# main.net
KiCad netlist of a schematic drawn in Altium Designer
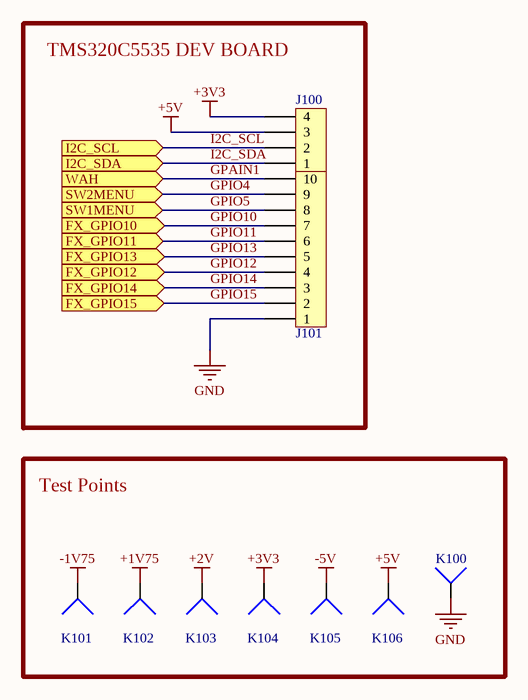
[diagram p0: main.SchDoc]

(export (version "E")
  (design (tool "Eeschema 10.0.6"))
  (components
    (comp (ref "J100")
      (value "Header 1x4")
      (footprint "Header 1x4")
      (libsource (lib "AAURacing") (part "Header 1x4"))
    )
    (comp (ref "J101")
      (value "Header 1x10")
      (footprint "Header 1x10")
      (libsource (lib "AAURacing") (part "Header 1x10"))
    )
    (comp (ref "K100") (value "Wire") (footprint "Wire 1.5mm") (libsource (lib "AAURacing") (part "Wire")))
    (comp (ref "K101") (value "Wire") (footprint "Wire 1.5mm") (libsource (lib "AAURacing") (part "Wire")))
    (comp (ref "K102") (value "Wire") (footprint "Wire 1.5mm") (libsource (lib "AAURacing") (part "Wire")))
    (comp (ref "K103") (value "Wire") (footprint "Wire 1.5mm") (libsource (lib "AAURacing") (part "Wire")))
    (comp (ref "K104") (value "Wire") (footprint "Wire 1.5mm") (libsource (lib "AAURacing") (part "Wire")))
    (comp (ref "K105") (value "Wire") (footprint "Wire 1.5mm") (libsource (lib "AAURacing") (part "Wire")))
    (comp (ref "K106") (value "Wire") (footprint "Wire 1.5mm") (libsource (lib "AAURacing") (part "Wire")))
  )
  (nets
    (net (code "1") (name "+1V75") (class "Default")
      (node (ref "K102") (pin "1") (pinfunction "1_1") (pintype "passive"))
    )
    (net (code "2") (name "+2V") (class "Default")
      (node (ref "K103") (pin "1") (pinfunction "1_1") (pintype "passive"))
    )
    (net (code "3") (name "+3V3") (class "Default")
      (node (ref "J100") (pin "4") (pinfunction "4_4") (pintype "passive"))
      (node (ref "K104") (pin "1") (pinfunction "1_1") (pintype "passive"))
    )
    (net (code "4") (name "+5V") (class "Default")
      (node (ref "J100") (pin "3") (pinfunction "3_3") (pintype "passive"))
      (node (ref "K106") (pin "1") (pinfunction "1_1") (pintype "passive"))
    )
    (net (code "5") (name "-1V75") (class "Default")
      (node (ref "K101") (pin "1") (pinfunction "1_1") (pintype "passive"))
    )
    (net (code "6") (name "-5V") (class "Default")
      (node (ref "K105") (pin "1") (pinfunction "1_1") (pintype "passive"))
    )
    (net (code "7") (name "/GPAIN1") (class "Default")
      (node (ref "J101") (pin "10") (pinfunction "10_10") (pintype "passive"))
    )
    (net (code "8") (name "/GPIO4") (class "Default")
      (node (ref "J101") (pin "9") (pinfunction "9_9") (pintype "passive"))
    )
    (net (code "9") (name "/GPIO5") (class "Default")
      (node (ref "J101") (pin "8") (pinfunction "8_8") (pintype "passive"))
    )
    (net (code "10") (name "/GPIO10") (class "Default")
      (node (ref "J101") (pin "7") (pinfunction "7_7") (pintype "passive"))
    )
    (net (code "11") (name "/GPIO11") (class "Default")
      (node (ref "J101") (pin "6") (pinfunction "6_6") (pintype "passive"))
    )
    (net (code "12") (name "/GPIO12") (class "Default")
      (node (ref "J101") (pin "4") (pinfunction "4_4") (pintype "passive"))
    )
    (net (code "13") (name "/GPIO13") (class "Default")
      (node (ref "J101") (pin "5") (pinfunction "5_5") (pintype "passive"))
    )
    (net (code "14") (name "/GPIO14") (class "Default")
      (node (ref "J101") (pin "3") (pinfunction "3_3") (pintype "passive"))
    )
    (net (code "15") (name "/GPIO15") (class "Default")
      (node (ref "J101") (pin "2") (pinfunction "2_2") (pintype "passive"))
    )
    (net (code "16") (name "/I2C_SCL") (class "Default")
      (node (ref "J100") (pin "2") (pinfunction "2_2") (pintype "passive"))
    )
    (net (code "17") (name "/I2C_SDA") (class "Default")
      (node (ref "J100") (pin "1") (pinfunction "1_1") (pintype "passive"))
    )
    (net (code "18") (name "GND") (class "Default")
      (node (ref "J101") (pin "1") (pinfunction "1_1") (pintype "passive"))
      (node (ref "K100") (pin "1") (pinfunction "1_1") (pintype "passive"))
    )
  )
)
